# BLE_--_HM-10_--_Carduino_Breakout_v1_0_3.net
KiCad netlist of a schematic drawn in EAGLE
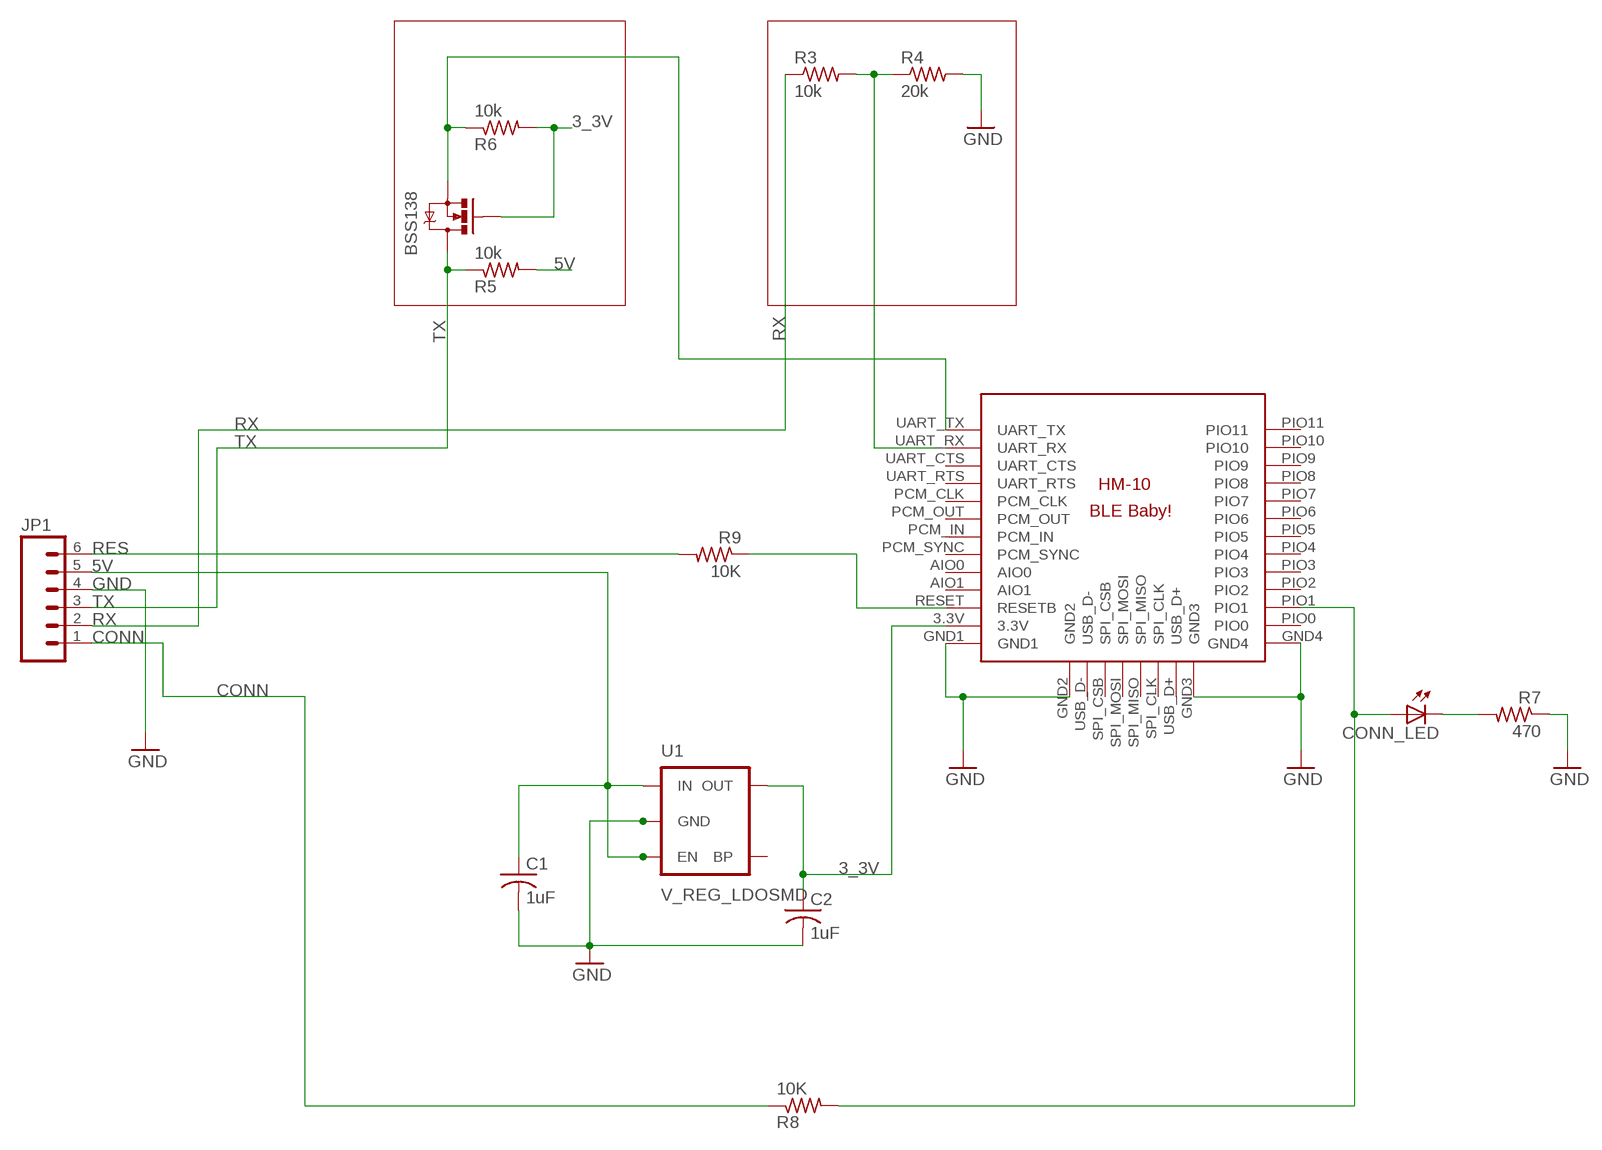
[diagram p0: schematic, sheet 1]

(export (version "E")
  (design (tool "Eeschema 10.0.6"))
  (components
    (comp (ref "BSS138")
      (value "MOSFET-NCHANNELSMD")
      (footprint "eagle-import:SOT23-3")
      (libsource (lib "eagle-import") (part "MOSFET-NCHANNELSMD"))
    )
    (comp (ref "C1")
      (value "1uF")
      (footprint "eagle-import:C0402")
      (libsource (lib "eagle-import") (part "C-USC0402"))
    )
    (comp (ref "C2")
      (value "1uF")
      (footprint "eagle-import:C0402")
      (libsource (lib "eagle-import") (part "C-USC0402"))
    )
    (comp (ref "CONN_LED")
      (value "LED0603")
      (footprint "eagle-import:LED-0603")
      (libsource (lib "eagle-import") (part "LED0603"))
    )
    (comp (ref "JP1")
      (value "M06SIP")
      (footprint "eagle-import:1X06")
      (libsource (lib "eagle-import") (part "M06SIP"))
    )
    (comp (ref "R3")
      (value "10k")
      (footprint "eagle-import:R0402")
      (libsource (lib "eagle-import") (part "R-US_R0402"))
    )
    (comp (ref "R4")
      (value "20k")
      (footprint "eagle-import:R0402")
      (libsource (lib "eagle-import") (part "R-US_R0402"))
    )
    (comp (ref "R5")
      (value "10k")
      (footprint "eagle-import:R0402")
      (libsource (lib "eagle-import") (part "R-US_R0402"))
    )
    (comp (ref "R6")
      (value "10k")
      (footprint "eagle-import:R0402")
      (libsource (lib "eagle-import") (part "R-US_R0402"))
    )
    (comp (ref "R7")
      (value "470")
      (footprint "eagle-import:R0402")
      (libsource (lib "eagle-import") (part "R-US_R0402"))
    )
    (comp (ref "R8")
      (value "10K")
      (footprint "eagle-import:R0402")
      (libsource (lib "eagle-import") (part "R-US_R0402"))
    )
    (comp (ref "R9")
      (value "10K")
      (footprint "eagle-import:R0402")
      (libsource (lib "eagle-import") (part "R-US_R0402"))
    )
    (comp (ref "U$1")
      (value "BLE-HM-10")
      (footprint "eagle-import:BLE-HM-10")
      (libsource (lib "eagle-import") (part "BLE-HM-10"))
    )
    (comp (ref "U1")
      (value "V_REG_LDOSMD")
      (footprint "eagle-import:SOT23-5")
      (libsource (lib "eagle-import") (part "V_REG_LDOSMD"))
    )
  )
  (nets
    (net (code "1") (name "/3_3V") (class "Default")
      (node (ref "BSS138") (pin "1") (pinfunction "G_1") (pintype "passive"))
      (node (ref "C2") (pin "1") (pinfunction "1_1") (pintype "passive"))
      (node (ref "R6") (pin "2") (pinfunction "2_2") (pintype "passive"))
      (node (ref "U$1") (pin "3.3V") (pinfunction "3.3V_3.3V") (pintype "bidirectional"))
      (node (ref "U1") (pin "5") (pinfunction "OUT_5") (pintype "passive"))
    )
    (net (code "2") (name "/5V") (class "Default")
      (node (ref "C1") (pin "1") (pinfunction "1_1") (pintype "passive"))
      (node (ref "JP1") (pin "5") (pinfunction "5_5") (pintype "passive"))
      (node (ref "R5") (pin "2") (pinfunction "2_2") (pintype "passive"))
      (node (ref "U1") (pin "1") (pinfunction "IN_1") (pintype "input"))
      (node (ref "U1") (pin "3") (pinfunction "EN_3") (pintype "input"))
    )
    (net (code "3") (name "/CONN") (class "Default")
      (node (ref "JP1") (pin "1") (pinfunction "1_1") (pintype "passive"))
      (node (ref "R8") (pin "1") (pinfunction "1_1") (pintype "passive"))
    )
    (net (code "4") (name "/RES") (class "Default")
      (node (ref "R9") (pin "1") (pinfunction "1_1") (pintype "passive"))
      (node (ref "U$1") (pin "RESET") (pinfunction "RESETB_RESET") (pintype "bidirectional"))
    )
    (net (code "5") (name "/RX") (class "Default")
      (node (ref "JP1") (pin "2") (pinfunction "2_2") (pintype "passive"))
      (node (ref "R3") (pin "1") (pinfunction "1_1") (pintype "passive"))
    )
    (net (code "6") (name "/TX") (class "Default")
      (node (ref "BSS138") (pin "3") (pinfunction "D_3") (pintype "passive"))
      (node (ref "JP1") (pin "3") (pinfunction "3_3") (pintype "passive"))
      (node (ref "R5") (pin "1") (pinfunction "1_1") (pintype "passive"))
    )
    (net (code "7") (name "GND") (class "Default")
      (node (ref "C1") (pin "2") (pinfunction "2_2") (pintype "passive"))
      (node (ref "C2") (pin "2") (pinfunction "2_2") (pintype "passive"))
      (node (ref "JP1") (pin "4") (pinfunction "4_4") (pintype "passive"))
      (node (ref "R4") (pin "2") (pinfunction "2_2") (pintype "passive"))
      (node (ref "R7") (pin "1") (pinfunction "1_1") (pintype "passive"))
      (node (ref "U$1") (pin "GND1") (pinfunction "GND1_GND1") (pintype "bidirectional"))
      (node (ref "U$1") (pin "GND2") (pinfunction "GND2_GND2") (pintype "bidirectional"))
      (node (ref "U$1") (pin "GND3") (pinfunction "GND3_GND3") (pintype "bidirectional"))
      (node (ref "U$1") (pin "GND4") (pinfunction "GND4_GND4") (pintype "bidirectional"))
      (node (ref "U1") (pin "2") (pinfunction "GND_2") (pintype "input"))
    )
    (net (code "8") (name "Net-(BSS138-S)") (class "Default")
      (node (ref "BSS138") (pin "2") (pinfunction "S_2") (pintype "passive"))
      (node (ref "R6") (pin "1") (pinfunction "1_1") (pintype "passive"))
      (node (ref "U$1") (pin "UART_TX") (pinfunction "UART_TX_UART_TX") (pintype "bidirectional"))
    )
    (net (code "9") (name "Net-(CONN_LED-PadA)") (class "Default")
      (node (ref "CONN_LED") (pin "A") (pinfunction "A_A") (pintype "passive"))
      (node (ref "R8") (pin "2") (pinfunction "2_2") (pintype "passive"))
      (node (ref "U$1") (pin "PIO1") (pinfunction "PIO1_PIO1") (pintype "bidirectional"))
    )
    (net (code "10") (name "Net-(CONN_LED-PadC)") (class "Default")
      (node (ref "CONN_LED") (pin "C") (pinfunction "C_C") (pintype "passive"))
      (node (ref "R7") (pin "2") (pinfunction "2_2") (pintype "passive"))
    )
    (net (code "11") (name "Net-(JP1-Pad6)") (class "Default")
      (node (ref "JP1") (pin "6") (pinfunction "6_6") (pintype "passive"))
      (node (ref "R9") (pin "2") (pinfunction "2_2") (pintype "passive"))
    )
    (net (code "12") (name "Net-(R3-Pad2)") (class "Default")
      (node (ref "R3") (pin "2") (pinfunction "2_2") (pintype "passive"))
      (node (ref "R4") (pin "1") (pinfunction "1_1") (pintype "passive"))
      (node (ref "U$1") (pin "UART_RX") (pinfunction "UART_RX_UART_RX") (pintype "bidirectional"))
    )
    (net (code "13") (name "unconnected-(U$1-PadAIO0)") (class "Default")
      (node (ref "U$1") (pin "AIO0") (pinfunction "AIO0_AIO0") (pintype "bidirectional"))
    )
    (net (code "14") (name "unconnected-(U$1-PadAIO1)") (class "Default")
      (node (ref "U$1") (pin "AIO1") (pinfunction "AIO1_AIO1") (pintype "bidirectional"))
    )
    (net (code "15") (name "unconnected-(U$1-PadPCM_CLK)") (class "Default")
      (node (ref "U$1") (pin "PCM_CLK") (pinfunction "PCM_CLK_PCM_CLK") (pintype "bidirectional"))
    )
    (net (code "16") (name "unconnected-(U$1-PadPCM_IN)") (class "Default")
      (node (ref "U$1") (pin "PCM_IN") (pinfunction "PCM_IN_PCM_IN") (pintype "bidirectional"))
    )
    (net (code "17") (name "unconnected-(U$1-PadPCM_OUT)") (class "Default")
      (node (ref "U$1") (pin "PCM_OUT") (pinfunction "PCM_OUT_PCM_OUT") (pintype "bidirectional"))
    )
    (net (code "18") (name "unconnected-(U$1-PadPCM_SYNC)") (class "Default")
      (node (ref "U$1") (pin "PCM_SYNC") (pinfunction "PCM_SYNC_PCM_SYNC") (pintype "bidirectional"))
    )
    (net (code "19") (name "unconnected-(U$1-PadPIO0)") (class "Default")
      (node (ref "U$1") (pin "PIO0") (pinfunction "PIO0_PIO0") (pintype "bidirectional"))
    )
    (net (code "20") (name "unconnected-(U$1-PadPIO2)") (class "Default")
      (node (ref "U$1") (pin "PIO2") (pinfunction "PIO2_PIO2") (pintype "bidirectional"))
    )
    (net (code "21") (name "unconnected-(U$1-PadPIO3)") (class "Default")
      (node (ref "U$1") (pin "PIO3") (pinfunction "PIO3_PIO3") (pintype "bidirectional"))
    )
    (net (code "22") (name "unconnected-(U$1-PadPIO4)") (class "Default")
      (node (ref "U$1") (pin "PIO4") (pinfunction "PIO4_PIO4") (pintype "bidirectional"))
    )
    (net (code "23") (name "unconnected-(U$1-PadPIO5)") (class "Default")
      (node (ref "U$1") (pin "PIO5") (pinfunction "PIO5_PIO5") (pintype "bidirectional"))
    )
    (net (code "24") (name "unconnected-(U$1-PadPIO6)") (class "Default")
      (node (ref "U$1") (pin "PIO6") (pinfunction "PIO6_PIO6") (pintype "bidirectional"))
    )
    (net (code "25") (name "unconnected-(U$1-PadPIO7)") (class "Default")
      (node (ref "U$1") (pin "PIO7") (pinfunction "PIO7_PIO7") (pintype "bidirectional"))
    )
    (net (code "26") (name "unconnected-(U$1-PadPIO8)") (class "Default")
      (node (ref "U$1") (pin "PIO8") (pinfunction "PIO8_PIO8") (pintype "bidirectional"))
    )
    (net (code "27") (name "unconnected-(U$1-PadPIO9)") (class "Default")
      (node (ref "U$1") (pin "PIO9") (pinfunction "PIO9_PIO9") (pintype "bidirectional"))
    )
    (net (code "28") (name "unconnected-(U$1-PadPIO10)") (class "Default")
      (node (ref "U$1") (pin "PIO10") (pinfunction "PIO10_PIO10") (pintype "bidirectional"))
    )
    (net (code "29") (name "unconnected-(U$1-PadPIO11)") (class "Default")
      (node (ref "U$1") (pin "PIO11") (pinfunction "PIO11_PIO11") (pintype "bidirectional"))
    )
    (net (code "30") (name "unconnected-(U$1-PadSPI_CLK)") (class "Default")
      (node (ref "U$1") (pin "SPI_CLK") (pinfunction "SPI_CLK_SPI_CLK") (pintype "bidirectional"))
    )
    (net (code "31") (name "unconnected-(U$1-PadSPI_CSB)") (class "Default")
      (node (ref "U$1") (pin "SPI_CSB") (pinfunction "SPI_CSB_SPI_CSB") (pintype "bidirectional"))
    )
    (net (code "32") (name "unconnected-(U$1-PadSPI_MISO)") (class "Default")
      (node (ref "U$1") (pin "SPI_MISO") (pinfunction "SPI_MISO_SPI_MISO") (pintype "bidirectional"))
    )
    (net (code "33") (name "unconnected-(U$1-PadSPI_MOSI)") (class "Default")
      (node (ref "U$1") (pin "SPI_MOSI") (pinfunction "SPI_MOSI_SPI_MOSI") (pintype "bidirectional"))
    )
    (net (code "34") (name "unconnected-(U$1-PadUART_CTS)") (class "Default")
      (node (ref "U$1") (pin "UART_CTS") (pinfunction "UART_CTS_UART_CTS") (pintype "bidirectional"))
    )
    (net (code "35") (name "unconnected-(U$1-PadUART_RTS)") (class "Default")
      (node (ref "U$1") (pin "UART_RTS") (pinfunction "UART_RTS_UART_RTS") (pintype "bidirectional"))
    )
    (net (code "36") (name "unconnected-(U$1-PadUSB_D+)") (class "Default")
      (node (ref "U$1") (pin "USB_D+") (pinfunction "USB_D+_USB_D+") (pintype "bidirectional"))
    )
    (net (code "37") (name "unconnected-(U$1-PadUSB_D-)") (class "Default")
      (node (ref "U$1") (pin "USB_D-") (pinfunction "USB_D-_USB_D-") (pintype "bidirectional"))
    )
    (net (code "38") (name "unconnected-(U1-BP-Pad4)") (class "Default")
      (node (ref "U1") (pin "4") (pinfunction "BP_4") (pintype "input"))
    )
  )
)
